# loraModule.net
KiCad netlist of a schematic drawn in Altium Designer
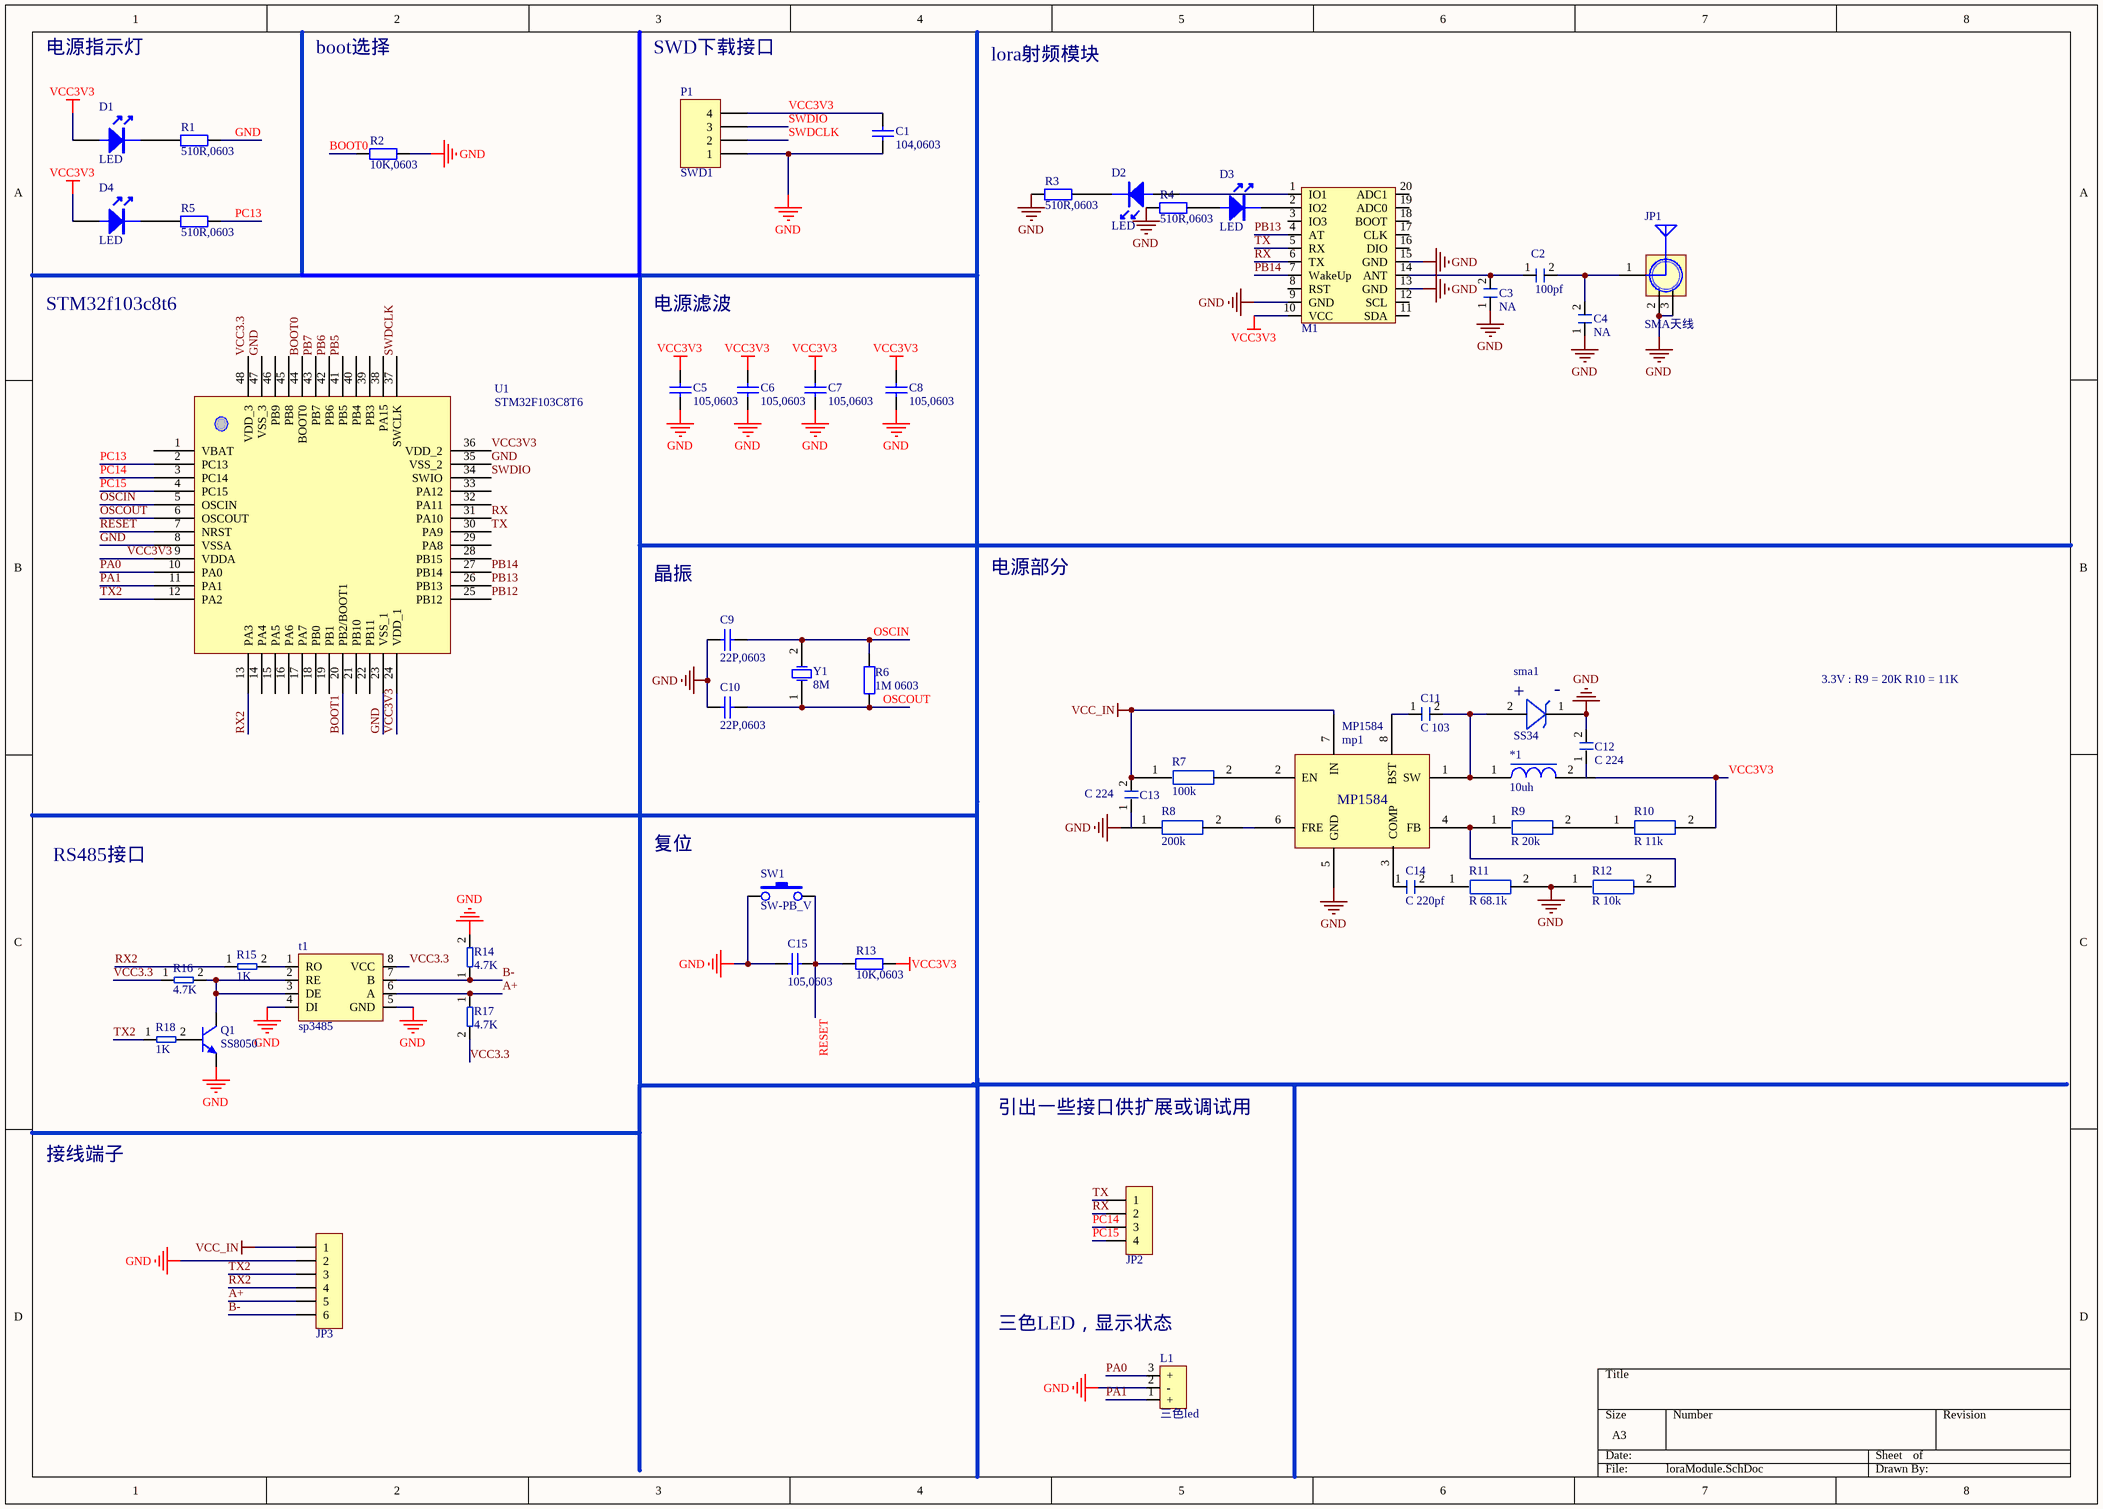
[diagram p0: loraModule.SchDoc]

(export (version "E")
  (design (tool "Eeschema 10.0.6"))
  (components
    (comp (ref "*1") (value "10uh") (footprint "inductance") (libsource (lib "mp1584") (part "inductance")))
    (comp (ref "C1")
      (value "104,0603")
      (footprint "C 0603")
      (description "Capacitor")
      (fields (field (name "PUBLISHER") "Altium Limited"))
      (libsource (lib "STM32F103C8T6") (part "Cap"))
    )
    (comp (ref "C2") (value "100pf") (footprint "C 0603") (libsource (lib "mp1584") (part "C 0603")))
    (comp (ref "C3") (value "NA") (footprint "C 0603") (libsource (lib "mp1584") (part "C 0603")))
    (comp (ref "C4") (value "NA") (footprint "C 0603") (libsource (lib "mp1584") (part "C 0603")))
    (comp (ref "C5")
      (value "105,0603")
      (footprint "C 0603")
      (description "Capacitor")
      (fields (field (name "PUBLISHER") "Altium Limited"))
      (libsource (lib "STM32F103C8T6") (part "Cap"))
    )
    (comp (ref "C6")
      (value "105,0603")
      (footprint "C 0603")
      (description "Capacitor")
      (fields (field (name "PUBLISHER") "Altium Limited"))
      (libsource (lib "STM32F103C8T6") (part "Cap"))
    )
    (comp (ref "C7")
      (value "105,0603")
      (footprint "C 0603")
      (description "Capacitor")
      (fields (field (name "PUBLISHER") "Altium Limited"))
      (libsource (lib "STM32F103C8T6") (part "Cap"))
    )
    (comp (ref "C8")
      (value "105,0603")
      (footprint "C 0603")
      (description "Capacitor")
      (fields (field (name "PUBLISHER") "Altium Limited"))
      (libsource (lib "STM32F103C8T6") (part "Cap"))
    )
    (comp (ref "C9")
      (value "22P,0603")
      (footprint "C 0603")
      (description "Capacitor")
      (fields (field (name "PUBLISHER") "Altium Limited"))
      (libsource (lib "STM32F103C8T6") (part "Cap"))
    )
    (comp (ref "C10")
      (value "22P,0603")
      (footprint "C 0603")
      (description "Capacitor")
      (fields (field (name "PUBLISHER") "Altium Limited"))
      (libsource (lib "STM32F103C8T6") (part "Cap"))
    )
    (comp (ref "C11") (value "C 103") (footprint "C 0603") (libsource (lib "mp1584") (part "C 0603")))
    (comp (ref "C12") (value "C 224") (footprint "C 1206") (libsource (lib "mp1584") (part "C 1206")))
    (comp (ref "C13") (value "C 224") (footprint "C 1206") (libsource (lib "mp1584") (part "C 1206")))
    (comp (ref "C14") (value "C 220pf") (footprint "C 0603") (libsource (lib "mp1584") (part "C 0603")))
    (comp (ref "C15")
      (value "105,0603")
      (footprint "C 0603")
      (description "Capacitor")
      (fields (field (name "PUBLISHER") "Altium Limited"))
      (libsource (lib "STM32F103C8T6") (part "Cap"))
    )
    (comp (ref "D1") (value "LED") (footprint "LED 0805G") (libsource (lib "STM32F103C8T6") (part "LED")))
    (comp (ref "D2") (value "LED") (footprint "LED 0805G") (libsource (lib "STM32F103C8T6") (part "LED")))
    (comp (ref "D3") (value "LED") (footprint "LED 0805G") (libsource (lib "STM32F103C8T6") (part "LED")))
    (comp (ref "D4") (value "LED") (footprint "LED 0805G") (libsource (lib "STM32F103C8T6") (part "LED")))
    (comp (ref "JP1")
      (value "SMA天线")
      (footprint "SMA-KE-LI")
      (description "SMA-2.4G射频天线接口")
      (libsource (lib "14.1 - 天线") (part "SMA"))
    )
    (comp (ref "JP2")
      (value "HDR-1X4")
      (footprint "XH2.54-WI-4P")
      (description "4P接插件")
      (libsource (lib "4.5   - 接插件-脚距2.54") (part "Header 4"))
    )
    (comp (ref "JP3")
      (value "HDR-1X6")
      (footprint "XH-3.55")
      (description "6P接插件")
      (libsource (lib "4.5   - 接插件-脚距2.54") (part "Header 6"))
    )
    (comp (ref "L1")
      (value "三色led")
      (footprint "三色led - duplicate")
      (libsource (lib "mp1584") (part "三色led"))
    )
    (comp (ref "M1") (value "M-HL10") (footprint "M-HL10") (libsource (lib "mp1584") (part "M-HL10")))
    (comp (ref "mp1") (value "MP1584") (footprint "mp1584") (libsource (lib "mp1584") (part "M?")))
    (comp (ref "P1")
      (value "SWD1")
      (footprint "HDR-1X4_H")
      (description "Header, 4-Pin")
      (fields (field (name "PUBLISHER") "Altium Limited"))
      (libsource (lib "STM32F103C8T6") (part "Header 4"))
    )
    (comp (ref "Q1")
      (value "SS8050")
      (footprint "SOT-23")
      (description "高频放大-NPN型")
      (libsource (lib "6.2   - 三极管") (part "8050-SMD"))
    )
    (comp (ref "R1")
      (value "510R,0603")
      (footprint "R 0603")
      (description "Resistor")
      (fields (field (name "PUBLISHER") "Altium Limited"))
      (libsource (lib "") (part "Res2_1"))
    )
    (comp (ref "R2")
      (value "10K,0603")
      (footprint "R 0603")
      (description "Resistor")
      (fields (field (name "PUBLISHER") "Altium Limited"))
      (libsource (lib "") (part "Res2_1"))
    )
    (comp (ref "R3")
      (value "510R,0603")
      (footprint "R 0603")
      (description "Resistor")
      (fields (field (name "PUBLISHER") "Altium Limited"))
      (libsource (lib "") (part "Res2_1"))
    )
    (comp (ref "R4")
      (value "510R,0603")
      (footprint "R 0603")
      (description "Resistor")
      (fields (field (name "PUBLISHER") "Altium Limited"))
      (libsource (lib "") (part "Res2_1"))
    )
    (comp (ref "R5")
      (value "510R,0603")
      (footprint "R 0603")
      (description "Resistor")
      (fields (field (name "PUBLISHER") "Altium Limited"))
      (libsource (lib "") (part "Res2_1"))
    )
    (comp (ref "R6")
      (value "1M 0603")
      (footprint "R 0603")
      (description "Resistor")
      (fields (field (name "PUBLISHER") "Altium Limited"))
      (libsource (lib "STM32F103C8T6") (part "Res2"))
    )
    (comp (ref "R7") (value "100k") (footprint "R 0603") (libsource (lib "mp1584") (part "R?")))
    (comp (ref "R8") (value "200k") (footprint "R 0603") (libsource (lib "mp1584") (part "R?")))
    (comp (ref "R9") (value "R 20k") (footprint "R 0603") (libsource (lib "mp1584") (part "R 0603")))
    (comp (ref "R10") (value "R 11k") (footprint "R 0603") (libsource (lib "mp1584") (part "R 0603")))
    (comp (ref "R11") (value "R 68.1k") (footprint "R 0603") (libsource (lib "mp1584") (part "R 0603")))
    (comp (ref "R12") (value "R 10k") (footprint "R 0603") (libsource (lib "mp1584") (part "R 0603")))
    (comp (ref "R13")
      (value "10K,0603")
      (footprint "R 0603")
      (description "Resistor")
      (fields (field (name "PUBLISHER") "Altium Limited"))
      (libsource (lib "") (part "Res2_1"))
    )
    (comp (ref "R14") (value "4.7K") (footprint "R 0805") (libsource (lib "mp1584") (part "R 0805")))
    (comp (ref "R15") (value "1K") (footprint "R 0805") (libsource (lib "mp1584") (part "R 0805")))
    (comp (ref "R16") (value "4.7K") (footprint "R 0805") (libsource (lib "mp1584") (part "R 0805")))
    (comp (ref "R17") (value "4.7K") (footprint "R 0805") (libsource (lib "mp1584") (part "R 0805")))
    (comp (ref "R18") (value "1K") (footprint "R 0805") (libsource (lib "mp1584") (part "R 0805")))
    (comp (ref "sma1") (value "SS34") (footprint "SMA") (libsource (lib "mp1584") (part "s?")))
    (comp (ref "SW1")
      (value "SW-PB_V")
      (footprint "TSW SMD-3*6*2.5")
      (description "SWITCH")
      (libsource (lib "STM32F103C8T6") (part "SW-PB_V"))
    )
    (comp (ref "t1") (value "sp3485") (footprint "sp3485") (libsource (lib "mp1584") (part "transistor")))
    (comp (ref "U1")
      (value "STM32F103C8T6")
      (footprint "TQFP48 7x7_L")
      (libsource (lib "PCB_Project_4") (part "STM32F103C8T6"))
    )
    (comp (ref "Y1")
      (value "8M")
      (footprint "XTAL-49S DIP")
      (description "Crystal Oscillator")
      (fields (field (name "PUBLISHER") "Altium Limited"))
      (libsource (lib "STM32F103C8T6") (part "XTAL"))
    )
  )
  (nets
    (net (code "1") (name "/A+") (class "Default")
      (node (ref "JP3") (pin "5") (pinfunction "5_5") (pintype "passive"))
      (node (ref "R17") (pin "1") (pinfunction "1_1") (pintype "passive"))
      (node (ref "t1") (pin "6") (pinfunction "A_6") (pintype "passive"))
    )
    (net (code "2") (name "/B-") (class "Default")
      (node (ref "JP3") (pin "6") (pinfunction "6_6") (pintype "passive"))
      (node (ref "R14") (pin "1") (pinfunction "1_1") (pintype "passive"))
      (node (ref "t1") (pin "7") (pinfunction "B_7") (pintype "passive"))
    )
    (net (code "3") (name "/BOOT0") (class "Default")
      (node (ref "R2") (pin "1") (pinfunction "1_1") (pintype "passive"))
      (node (ref "U1") (pin "44") (pinfunction "BOOT0_44") (pintype "passive"))
    )
    (net (code "4") (name "/BOOT1") (class "Default")
      (node (ref "U1") (pin "20") (pinfunction "PB2/BOOT1_20") (pintype "passive"))
    )
    (net (code "5") (name "/OSCIN") (class "Default")
      (node (ref "C9") (pin "1") (pinfunction "1_1") (pintype "passive"))
      (node (ref "R6") (pin "2") (pinfunction "2_2") (pintype "passive"))
      (node (ref "U1") (pin "5") (pinfunction "OSCIN_5") (pintype "passive"))
      (node (ref "Y1") (pin "2") (pinfunction "OSC2_2") (pintype "passive"))
    )
    (net (code "6") (name "/OSCOUT") (class "Default")
      (node (ref "C10") (pin "1") (pinfunction "1_1") (pintype "passive"))
      (node (ref "R6") (pin "1") (pinfunction "1_1") (pintype "passive"))
      (node (ref "U1") (pin "6") (pinfunction "OSCOUT_6") (pintype "passive"))
      (node (ref "Y1") (pin "1") (pinfunction "OSC1_1") (pintype "passive"))
    )
    (net (code "7") (name "/PA0") (class "Default")
      (node (ref "L1") (pin "3") (pinfunction "+_3") (pintype "passive"))
      (node (ref "U1") (pin "10") (pinfunction "PA0_10") (pintype "passive"))
    )
    (net (code "8") (name "/PA1") (class "Default")
      (node (ref "L1") (pin "1") (pinfunction "+_1") (pintype "passive"))
      (node (ref "U1") (pin "11") (pinfunction "PA1_11") (pintype "passive"))
    )
    (net (code "9") (name "/PB5") (class "Default")
      (node (ref "U1") (pin "41") (pinfunction "PB5_41") (pintype "passive"))
    )
    (net (code "10") (name "/PB6") (class "Default")
      (node (ref "U1") (pin "42") (pinfunction "PB6_42") (pintype "passive"))
    )
    (net (code "11") (name "/PB7") (class "Default")
      (node (ref "U1") (pin "43") (pinfunction "PB7_43") (pintype "passive"))
    )
    (net (code "12") (name "/PB12") (class "Default")
      (node (ref "U1") (pin "25") (pinfunction "PB12_25") (pintype "passive"))
    )
    (net (code "13") (name "/PB13") (class "Default")
      (node (ref "M1") (pin "4") (pinfunction "AT_4") (pintype "passive"))
      (node (ref "U1") (pin "26") (pinfunction "PB13_26") (pintype "passive"))
    )
    (net (code "14") (name "/PB14") (class "Default")
      (node (ref "M1") (pin "7") (pinfunction "WakeUp_7") (pintype "passive"))
      (node (ref "U1") (pin "27") (pinfunction "PB14_27") (pintype "passive"))
    )
    (net (code "15") (name "/PC13") (class "Default")
      (node (ref "R5") (pin "2") (pinfunction "2_2") (pintype "passive"))
      (node (ref "U1") (pin "2") (pinfunction "PC13_2") (pintype "passive"))
    )
    (net (code "16") (name "/PC14") (class "Default")
      (node (ref "JP2") (pin "3") (pinfunction "3_3") (pintype "passive"))
      (node (ref "U1") (pin "3") (pinfunction "PC14_3") (pintype "passive"))
    )
    (net (code "17") (name "/PC15") (class "Default")
      (node (ref "JP2") (pin "4") (pinfunction "4_4") (pintype "passive"))
      (node (ref "U1") (pin "4") (pinfunction "PC15_4") (pintype "passive"))
    )
    (net (code "18") (name "/RESET") (class "Default")
      (node (ref "C15") (pin "2") (pinfunction "2_2") (pintype "passive"))
      (node (ref "R13") (pin "1") (pinfunction "1_1") (pintype "passive"))
      (node (ref "SW1") (pin "2") (pinfunction "2_2") (pintype "passive"))
      (node (ref "U1") (pin "7") (pinfunction "NRST_7") (pintype "passive"))
    )
    (net (code "19") (name "/RX") (class "Default")
      (node (ref "JP2") (pin "2") (pinfunction "2_2") (pintype "passive"))
      (node (ref "M1") (pin "6") (pinfunction "TX_6") (pintype "passive"))
      (node (ref "U1") (pin "31") (pinfunction "PA10_31") (pintype "passive"))
    )
    (net (code "20") (name "/RX2") (class "Default")
      (node (ref "JP3") (pin "4") (pinfunction "4_4") (pintype "passive"))
      (node (ref "R15") (pin "1") (pinfunction "1_1") (pintype "passive"))
      (node (ref "U1") (pin "13") (pinfunction "PA3_13") (pintype "passive"))
    )
    (net (code "21") (name "/SWDCLK") (class "Default")
      (node (ref "P1") (pin "2") (pinfunction "2_2") (pintype "passive"))
      (node (ref "U1") (pin "37") (pinfunction "SWCLK_37") (pintype "passive"))
    )
    (net (code "22") (name "/SWDIO") (class "Default")
      (node (ref "P1") (pin "3") (pinfunction "3_3") (pintype "passive"))
      (node (ref "U1") (pin "34") (pinfunction "SWIO_34") (pintype "passive"))
    )
    (net (code "23") (name "/TX") (class "Default")
      (node (ref "JP2") (pin "1") (pinfunction "1_1") (pintype "passive"))
      (node (ref "M1") (pin "5") (pinfunction "RX_5") (pintype "passive"))
      (node (ref "U1") (pin "30") (pinfunction "PA9_30") (pintype "passive"))
    )
    (net (code "24") (name "/TX2") (class "Default")
      (node (ref "JP3") (pin "3") (pinfunction "3_3") (pintype "passive"))
      (node (ref "R18") (pin "1") (pinfunction "1_1") (pintype "passive"))
      (node (ref "U1") (pin "12") (pinfunction "PA2_12") (pintype "passive"))
    )
    (net (code "25") (name "/VCC3.3") (class "Default")
      (node (ref "R16") (pin "1") (pinfunction "1_1") (pintype "passive"))
      (node (ref "R17") (pin "2") (pinfunction "2_2") (pintype "passive"))
      (node (ref "U1") (pin "48") (pinfunction "VDD_3_48") (pintype "passive"))
      (node (ref "t1") (pin "8") (pinfunction "VCC_8") (pintype "passive"))
    )
    (net (code "26") (name "GND") (class "Default")
      (node (ref "C1") (pin "1") (pinfunction "1_1") (pintype "passive"))
      (node (ref "C10") (pin "2") (pinfunction "2_2") (pintype "passive"))
      (node (ref "C12") (pin "2") (pinfunction "2_2") (pintype "passive"))
      (node (ref "C15") (pin "1") (pinfunction "1_1") (pintype "passive"))
      (node (ref "C3") (pin "1") (pinfunction "1_1") (pintype "passive"))
      (node (ref "C4") (pin "1") (pinfunction "1_1") (pintype "passive"))
      (node (ref "C5") (pin "1") (pinfunction "1_1") (pintype "passive"))
      (node (ref "C6") (pin "1") (pinfunction "1_1") (pintype "passive"))
      (node (ref "C7") (pin "1") (pinfunction "1_1") (pintype "passive"))
      (node (ref "C8") (pin "1") (pinfunction "1_1") (pintype "passive"))
      (node (ref "C9") (pin "2") (pinfunction "2_2") (pintype "passive"))
      (node (ref "JP1") (pin "2") (pinfunction "GND_2") (pintype "passive"))
      (node (ref "JP1") (pin "3") (pinfunction "GND_3") (pintype "passive"))
      (node (ref "JP3") (pin "2") (pinfunction "2_2") (pintype "passive"))
      (node (ref "L1") (pin "2") (pinfunction "-_2") (pintype "passive"))
      (node (ref "M1") (pin "13") (pinfunction "GND_13") (pintype "passive"))
      (node (ref "M1") (pin "15") (pinfunction "GND_15") (pintype "passive"))
      (node (ref "M1") (pin "9") (pinfunction "GND_9") (pintype "passive"))
      (node (ref "P1") (pin "1") (pinfunction "1_1") (pintype "passive"))
      (node (ref "Q1") (pin "2") (pinfunction "E_2") (pintype "passive"))
      (node (ref "R1") (pin "2") (pinfunction "2_2") (pintype "passive"))
      (node (ref "R11") (pin "2") (pinfunction "2_2") (pintype "passive"))
      (node (ref "R12") (pin "1") (pinfunction "1_1") (pintype "passive"))
      (node (ref "R14") (pin "2") (pinfunction "2_2") (pintype "passive"))
      (node (ref "R2") (pin "2") (pinfunction "2_2") (pintype "passive"))
      (node (ref "R3") (pin "1") (pinfunction "1_1") (pintype "passive"))
      (node (ref "R4") (pin "1") (pinfunction "1_1") (pintype "passive"))
      (node (ref "R8") (pin "1") (pinfunction "1_1") (pintype "passive"))
      (node (ref "SW1") (pin "1") (pinfunction "1_1") (pintype "passive"))
      (node (ref "U1") (pin "23") (pinfunction "VSS_1_23") (pintype "passive"))
      (node (ref "U1") (pin "35") (pinfunction "VSS_2_35") (pintype "passive"))
      (node (ref "U1") (pin "47") (pinfunction "VSS_3_47") (pintype "passive"))
      (node (ref "U1") (pin "8") (pinfunction "VSSA_8") (pintype "passive"))
      (node (ref "mp1") (pin "5") (pinfunction "GND_5") (pintype "passive"))
      (node (ref "sma1") (pin "1") (pinfunction "1_1") (pintype "passive"))
      (node (ref "t1") (pin "4") (pinfunction "DI_4") (pintype "passive"))
      (node (ref "t1") (pin "5") (pinfunction "GND_5") (pintype "passive"))
    )
    (net (code "27") (name "Net-(C14-Pad2)") (class "Default")
      (node (ref "C14") (pin "2") (pinfunction "2_2") (pintype "passive"))
      (node (ref "R11") (pin "1") (pinfunction "1_1") (pintype "passive"))
    )
    (net (code "28") (name "Net-(D1-Pad2)") (class "Default")
      (node (ref "D1") (pin "2") (pinfunction "2_2") (pintype "passive"))
      (node (ref "R1") (pin "1") (pinfunction "1_1") (pintype "passive"))
    )
    (net (code "29") (name "Net-(D2-Pad2)") (class "Default")
      (node (ref "D2") (pin "2") (pinfunction "2_2") (pintype "passive"))
      (node (ref "R3") (pin "2") (pinfunction "2_2") (pintype "passive"))
    )
    (net (code "30") (name "Net-(D4-Pad2)") (class "Default")
      (node (ref "D4") (pin "2") (pinfunction "2_2") (pintype "passive"))
      (node (ref "R5") (pin "1") (pinfunction "1_1") (pintype "passive"))
    )
    (net (code "31") (name "Net-(JP1-ANT)") (class "Default")
      (node (ref "C2") (pin "2") (pinfunction "2_2") (pintype "passive"))
      (node (ref "C4") (pin "2") (pinfunction "2_2") (pintype "passive"))
      (node (ref "JP1") (pin "1") (pinfunction "ANT_1") (pintype "passive"))
    )
    (net (code "32") (name "Net-(M1-ANT)") (class "Default")
      (node (ref "C2") (pin "1") (pinfunction "1_1") (pintype "passive"))
      (node (ref "C3") (pin "2") (pinfunction "2_2") (pintype "passive"))
      (node (ref "M1") (pin "14") (pinfunction "ANT_14") (pintype "passive"))
    )
    (net (code "33") (name "Net-(M1-IO1)") (class "Default")
      (node (ref "D2") (pin "1") (pinfunction "1_1") (pintype "passive"))
      (node (ref "M1") (pin "1") (pinfunction "IO1_1") (pintype "passive"))
    )
    (net (code "34") (name "Net-(M1-IO2)") (class "Default")
      (node (ref "D3") (pin "2") (pinfunction "2_2") (pintype "passive"))
      (node (ref "M1") (pin "2") (pinfunction "IO2_2") (pintype "passive"))
    )
    (net (code "35") (name "Net-(Q1-B)") (class "Default")
      (node (ref "Q1") (pin "1") (pinfunction "B_1") (pintype "passive"))
      (node (ref "R18") (pin "2") (pinfunction "2_2") (pintype "passive"))
    )
    (net (code "36") (name "Net-(Q1-C)") (class "Default")
      (node (ref "Q1") (pin "3") (pinfunction "C_3") (pintype "passive"))
      (node (ref "R16") (pin "2") (pinfunction "2_2") (pintype "passive"))
      (node (ref "t1") (pin "2") (pinfunction "RE_2") (pintype "passive"))
      (node (ref "t1") (pin "3") (pinfunction "DE_3") (pintype "passive"))
    )
    (net (code "37") (name "Net-(R10-Pad1)") (class "Default")
      (node (ref "R10") (pin "1") (pinfunction "1_1") (pintype "passive"))
      (node (ref "R9") (pin "2") (pinfunction "2_2") (pintype "passive"))
    )
    (net (code "38") (name "Net-(mp1-BST)") (class "Default")
      (node (ref "C11") (pin "1") (pinfunction "1_1") (pintype "passive"))
      (node (ref "mp1") (pin "8") (pinfunction "BST_8") (pintype "passive"))
    )
    (net (code "39") (name "Net-(mp1-COMP)") (class "Default")
      (node (ref "C14") (pin "1") (pinfunction "1_1") (pintype "passive"))
      (node (ref "mp1") (pin "3") (pinfunction "COMP_3") (pintype "passive"))
    )
    (net (code "40") (name "Net-(mp1-EN)") (class "Default")
      (node (ref "R7") (pin "2") (pinfunction "2_2") (pintype "passive"))
      (node (ref "mp1") (pin "2") (pinfunction "EN_2") (pintype "passive"))
    )
    (net (code "41") (name "Net-(mp1-FB)") (class "Default")
      (node (ref "R12") (pin "2") (pinfunction "2_2") (pintype "passive"))
      (node (ref "R9") (pin "1") (pinfunction "1_1") (pintype "passive"))
      (node (ref "mp1") (pin "4") (pinfunction "FB_4") (pintype "passive"))
    )
    (net (code "42") (name "Net-(mp1-FRE)") (class "Default")
      (node (ref "R8") (pin "2") (pinfunction "2_2") (pintype "passive"))
      (node (ref "mp1") (pin "6") (pinfunction "FRE_6") (pintype "passive"))
    )
    (net (code "43") (name "Net-(mp1-SW)") (class "Default")
      (node (ref "*1") (pin "1") (pinfunction "1_1") (pintype "passive"))
      (node (ref "C11") (pin "2") (pinfunction "2_2") (pintype "passive"))
      (node (ref "mp1") (pin "1") (pinfunction "SW_1") (pintype "passive"))
      (node (ref "sma1") (pin "2") (pinfunction "2_2") (pintype "passive"))
    )
    (net (code "44") (name "Net-(t1-RO)") (class "Default")
      (node (ref "R15") (pin "2") (pinfunction "2_2") (pintype "passive"))
      (node (ref "t1") (pin "1") (pinfunction "RO_1") (pintype "passive"))
    )
    (net (code "45") (name "VCC3V3") (class "Default")
      (node (ref "*1") (pin "2") (pinfunction "2_2") (pintype "passive"))
      (node (ref "C1") (pin "2") (pinfunction "2_2") (pintype "passive"))
      (node (ref "C5") (pin "2") (pinfunction "2_2") (pintype "passive"))
      (node (ref "C6") (pin "2") (pinfunction "2_2") (pintype "passive"))
      (node (ref "C7") (pin "2") (pinfunction "2_2") (pintype "passive"))
      (node (ref "C8") (pin "2") (pinfunction "2_2") (pintype "passive"))
      (node (ref "D1") (pin "1") (pinfunction "1_1") (pintype "passive"))
      (node (ref "D4") (pin "1") (pinfunction "1_1") (pintype "passive"))
      (node (ref "M1") (pin "10") (pinfunction "VCC_10") (pintype "passive"))
      (node (ref "P1") (pin "4") (pinfunction "4_4") (pintype "passive"))
      (node (ref "R10") (pin "2") (pinfunction "2_2") (pintype "passive"))
      (node (ref "R13") (pin "2") (pinfunction "2_2") (pintype "passive"))
      (node (ref "U1") (pin "24") (pinfunction "VDD_1_24") (pintype "passive"))
      (node (ref "U1") (pin "36") (pinfunction "VDD_2_36") (pintype "passive"))
      (node (ref "U1") (pin "9") (pinfunction "VDDA_9") (pintype "passive"))
    )
    (net (code "46") (name "VCC_IN") (class "Default")
      (node (ref "C13") (pin "2") (pinfunction "2_2") (pintype "passive"))
      (node (ref "JP3") (pin "1") (pinfunction "1_1") (pintype "passive"))
      (node (ref "R7") (pin "1") (pinfunction "1_1") (pintype "passive"))
      (node (ref "mp1") (pin "7") (pinfunction "IN_7") (pintype "passive"))
    )
    (net (code "47") (name "unconnected-(C12-Pad1)") (class "Default")
      (node (ref "C12") (pin "1") (pinfunction "1_1") (pintype "passive"))
    )
    (net (code "48") (name "unconnected-(C13-Pad1)") (class "Default")
      (node (ref "C13") (pin "1") (pinfunction "1_1") (pintype "passive"))
    )
    (net (code "49") (name "unconnected-(D3-Pad1)") (class "Default")
      (node (ref "D3") (pin "1") (pinfunction "1_1") (pintype "passive"))
    )
    (net (code "50") (name "unconnected-(M1-ADC0-Pad19)") (class "Default")
      (node (ref "M1") (pin "19") (pinfunction "ADC0_19") (pintype "passive"))
    )
    (net (code "51") (name "unconnected-(M1-ADC1-Pad20)") (class "Default")
      (node (ref "M1") (pin "20") (pinfunction "ADC1_20") (pintype "passive"))
    )
    (net (code "52") (name "unconnected-(M1-BOOT-Pad18)") (class "Default")
      (node (ref "M1") (pin "18") (pinfunction "BOOT_18") (pintype "passive"))
    )
    (net (code "53") (name "unconnected-(M1-CLK-Pad17)") (class "Default")
      (node (ref "M1") (pin "17") (pinfunction "CLK_17") (pintype "passive"))
    )
    (net (code "54") (name "unconnected-(M1-DIO-Pad16)") (class "Default")
      (node (ref "M1") (pin "16") (pinfunction "DIO_16") (pintype "passive"))
    )
    (net (code "55") (name "unconnected-(M1-IO3-Pad3)") (class "Default")
      (node (ref "M1") (pin "3") (pinfunction "IO3_3") (pintype "passive"))
    )
    (net (code "56") (name "unconnected-(M1-RST-Pad8)") (class "Default")
      (node (ref "M1") (pin "8") (pinfunction "RST_8") (pintype "passive"))
    )
    (net (code "57") (name "unconnected-(M1-SCL-Pad12)") (class "Default")
      (node (ref "M1") (pin "12") (pinfunction "SCL_12") (pintype "passive"))
    )
    (net (code "58") (name "unconnected-(M1-SDA-Pad11)") (class "Default")
      (node (ref "M1") (pin "11") (pinfunction "SDA_11") (pintype "passive"))
    )
    (net (code "59") (name "unconnected-(R4-Pad2)") (class "Default")
      (node (ref "R4") (pin "2") (pinfunction "2_2") (pintype "passive"))
    )
    (net (code "60") (name "unconnected-(U1-PA4-Pad14)") (class "Default")
      (node (ref "U1") (pin "14") (pinfunction "PA4_14") (pintype "passive"))
    )
    (net (code "61") (name "unconnected-(U1-PA5-Pad15)") (class "Default")
      (node (ref "U1") (pin "15") (pinfunction "PA5_15") (pintype "passive"))
    )
    (net (code "62") (name "unconnected-(U1-PA6-Pad16)") (class "Default")
      (node (ref "U1") (pin "16") (pinfunction "PA6_16") (pintype "passive"))
    )
    (net (code "63") (name "unconnected-(U1-PA7-Pad17)") (class "Default")
      (node (ref "U1") (pin "17") (pinfunction "PA7_17") (pintype "passive"))
    )
    (net (code "64") (name "unconnected-(U1-PA8-Pad29)") (class "Default")
      (node (ref "U1") (pin "29") (pinfunction "PA8_29") (pintype "passive"))
    )
    (net (code "65") (name "unconnected-(U1-PA11-Pad32)") (class "Default")
      (node (ref "U1") (pin "32") (pinfunction "PA11_32") (pintype "passive"))
    )
    (net (code "66") (name "unconnected-(U1-PA12-Pad33)") (class "Default")
      (node (ref "U1") (pin "33") (pinfunction "PA12_33") (pintype "passive"))
    )
    (net (code "67") (name "unconnected-(U1-PA15-Pad38)") (class "Default")
      (node (ref "U1") (pin "38") (pinfunction "PA15_38") (pintype "passive"))
    )
    (net (code "68") (name "unconnected-(U1-PB0-Pad18)") (class "Default")
      (node (ref "U1") (pin "18") (pinfunction "PB0_18") (pintype "passive"))
    )
    (net (code "69") (name "unconnected-(U1-PB1-Pad19)") (class "Default")
      (node (ref "U1") (pin "19") (pinfunction "PB1_19") (pintype "passive"))
    )
    (net (code "70") (name "unconnected-(U1-PB3-Pad39)") (class "Default")
      (node (ref "U1") (pin "39") (pinfunction "PB3_39") (pintype "passive"))
    )
    (net (code "71") (name "unconnected-(U1-PB4-Pad40)") (class "Default")
      (node (ref "U1") (pin "40") (pinfunction "PB4_40") (pintype "passive"))
    )
    (net (code "72") (name "unconnected-(U1-PB8-Pad45)") (class "Default")
      (node (ref "U1") (pin "45") (pinfunction "PB8_45") (pintype "passive"))
    )
    (net (code "73") (name "unconnected-(U1-PB9-Pad46)") (class "Default")
      (node (ref "U1") (pin "46") (pinfunction "PB9_46") (pintype "passive"))
    )
    (net (code "74") (name "unconnected-(U1-PB10-Pad21)") (class "Default")
      (node (ref "U1") (pin "21") (pinfunction "PB10_21") (pintype "passive"))
    )
    (net (code "75") (name "unconnected-(U1-PB11-Pad22)") (class "Default")
      (node (ref "U1") (pin "22") (pinfunction "PB11_22") (pintype "passive"))
    )
    (net (code "76") (name "unconnected-(U1-PB15-Pad28)") (class "Default")
      (node (ref "U1") (pin "28") (pinfunction "PB15_28") (pintype "passive"))
    )
    (net (code "77") (name "unconnected-(U1-VBAT-Pad1)") (class "Default")
      (node (ref "U1") (pin "1") (pinfunction "VBAT_1") (pintype "passive"))
    )
  )
)
